# mainboard.net
KiCad netlist of a schematic drawn in EAGLE
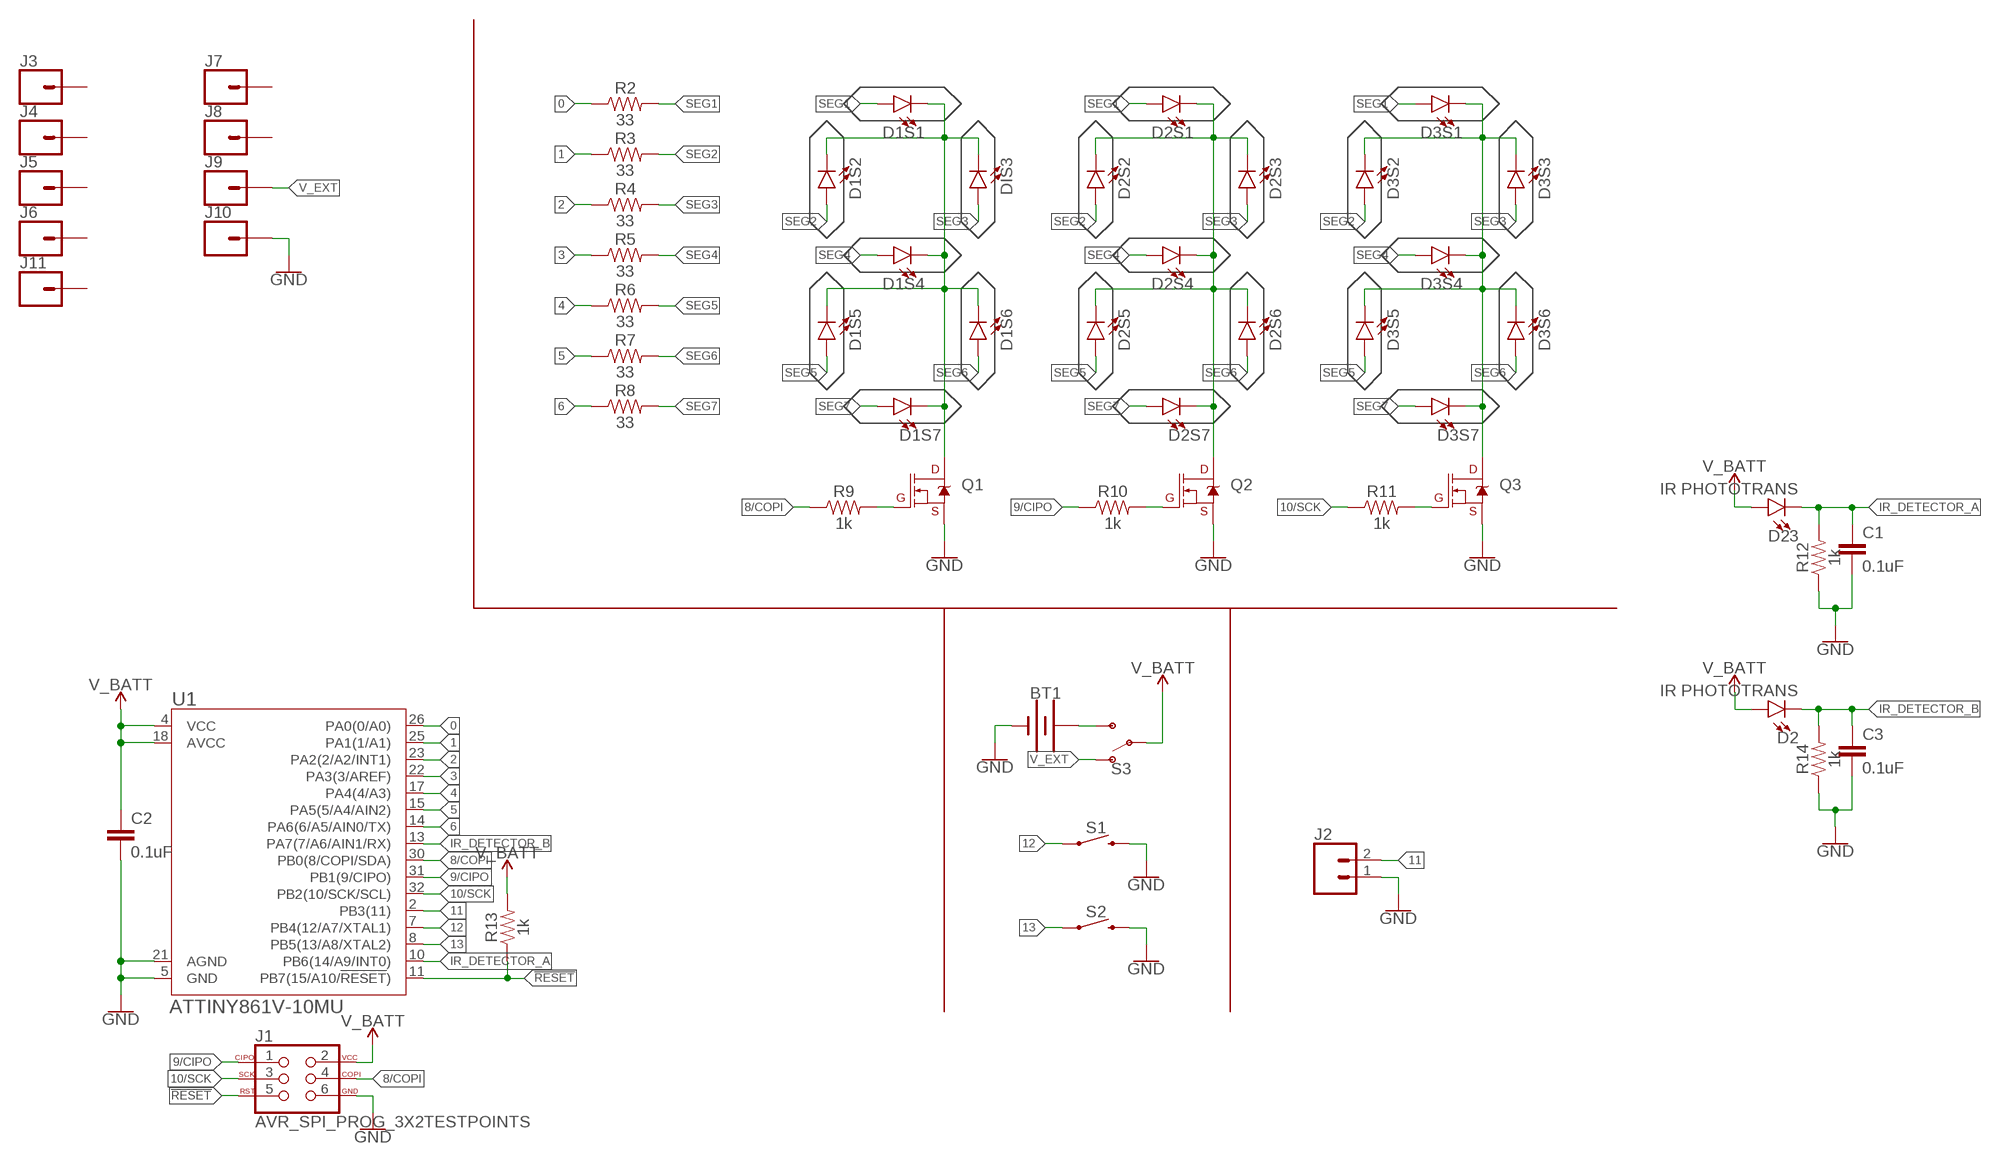
[diagram p0: schematic, sheet 1]

(export (version "E")
  (design (tool "Eeschema 10.0.6"))
  (components
    (comp (ref "BT1")
      (value "BATTERY-20MM_SMD_4LEGS_OVERPASTE_INNER")
      (footprint "eagle-import:BATTCON_20MM_4LEGS_OVERPASTE_INNER")
      (libsource (lib "eagle-import") (part "BATTERY-20MM_SMD_4LEGS_OVERPASTE_INNER"))
    )
    (comp (ref "C1")
      (value "0.1uF")
      (footprint "eagle-import:0603")
      (libsource (lib "eagle-import") (part "0.1UF-0603-25V-(+80/-20%)"))
    )
    (comp (ref "C2")
      (value "0.1uF")
      (footprint "eagle-import:0603")
      (libsource (lib "eagle-import") (part "0.1UF-0603-25V-(+80/-20%)"))
    )
    (comp (ref "C3")
      (value "0.1uF")
      (footprint "eagle-import:0603")
      (libsource (lib "eagle-import") (part "0.1UF-0603-25V-(+80/-20%)"))
    )
    (comp (ref "D1S1")
      (value "LED0603")
      (footprint "eagle-import:LED-0603")
      (libsource (lib "eagle-import") (part "LED0603"))
    )
    (comp (ref "D1S2")
      (value "LED0603")
      (footprint "eagle-import:LED-0603")
      (libsource (lib "eagle-import") (part "LED0603"))
    )
    (comp (ref "D1S4")
      (value "LED0603")
      (footprint "eagle-import:LED-0603")
      (libsource (lib "eagle-import") (part "LED0603"))
    )
    (comp (ref "D1S5")
      (value "LED0603")
      (footprint "eagle-import:LED-0603")
      (libsource (lib "eagle-import") (part "LED0603"))
    )
    (comp (ref "D1S6")
      (value "LED0603")
      (footprint "eagle-import:LED-0603")
      (libsource (lib "eagle-import") (part "LED0603"))
    )
    (comp (ref "D1S7")
      (value "LED0603")
      (footprint "eagle-import:LED-0603")
      (libsource (lib "eagle-import") (part "LED0603"))
    )
    (comp (ref "D2")
      (value "IR PHOTOTRANS")
      (footprint "eagle-import:LED-0603")
      (libsource (lib "eagle-import") (part "LED-IR0603"))
    )
    (comp (ref "D2S1")
      (value "LED0603")
      (footprint "eagle-import:LED-0603")
      (libsource (lib "eagle-import") (part "LED0603"))
    )
    (comp (ref "D2S2")
      (value "LED0603")
      (footprint "eagle-import:LED-0603")
      (libsource (lib "eagle-import") (part "LED0603"))
    )
    (comp (ref "D2S3")
      (value "LED0603")
      (footprint "eagle-import:LED-0603")
      (libsource (lib "eagle-import") (part "LED0603"))
    )
    (comp (ref "D2S4")
      (value "LED0603")
      (footprint "eagle-import:LED-0603")
      (libsource (lib "eagle-import") (part "LED0603"))
    )
    (comp (ref "D2S5")
      (value "LED0603")
      (footprint "eagle-import:LED-0603")
      (libsource (lib "eagle-import") (part "LED0603"))
    )
    (comp (ref "D2S6")
      (value "LED0603")
      (footprint "eagle-import:LED-0603")
      (libsource (lib "eagle-import") (part "LED0603"))
    )
    (comp (ref "D2S7")
      (value "LED0603")
      (footprint "eagle-import:LED-0603")
      (libsource (lib "eagle-import") (part "LED0603"))
    )
    (comp (ref "D3S1")
      (value "LED0603")
      (footprint "eagle-import:LED-0603")
      (libsource (lib "eagle-import") (part "LED0603"))
    )
    (comp (ref "D3S2")
      (value "LED0603")
      (footprint "eagle-import:LED-0603")
      (libsource (lib "eagle-import") (part "LED0603"))
    )
    (comp (ref "D3S3")
      (value "LED0603")
      (footprint "eagle-import:LED-0603")
      (libsource (lib "eagle-import") (part "LED0603"))
    )
    (comp (ref "D3S4")
      (value "LED0603")
      (footprint "eagle-import:LED-0603")
      (libsource (lib "eagle-import") (part "LED0603"))
    )
    (comp (ref "D3S5")
      (value "LED0603")
      (footprint "eagle-import:LED-0603")
      (libsource (lib "eagle-import") (part "LED0603"))
    )
    (comp (ref "D3S6")
      (value "LED0603")
      (footprint "eagle-import:LED-0603")
      (libsource (lib "eagle-import") (part "LED0603"))
    )
    (comp (ref "D3S7")
      (value "LED0603")
      (footprint "eagle-import:LED-0603")
      (libsource (lib "eagle-import") (part "LED0603"))
    )
    (comp (ref "D23")
      (value "IR PHOTOTRANS")
      (footprint "eagle-import:LED-0603")
      (libsource (lib "eagle-import") (part "LED-IR0603"))
    )
    (comp (ref "DIS3")
      (value "LED0603")
      (footprint "eagle-import:LED-0603")
      (libsource (lib "eagle-import") (part "LED0603"))
    )
    (comp (ref "J1")
      (value "AVR_SPI_PROG_3X2TESTPOINTS")
      (footprint "eagle-import:2X3_TEST_POINTS")
      (libsource (lib "eagle-import") (part "AVR_SPI_PROG_3X2TESTPOINTS"))
    )
    (comp (ref "J2")
      (value "CONN_02")
      (footprint "eagle-import:1X02")
      (libsource (lib "eagle-import") (part "CONN_02"))
    )
    (comp (ref "J3")
      (value "CONN_01")
      (footprint "eagle-import:1X01")
      (libsource (lib "eagle-import") (part "CONN_01"))
    )
    (comp (ref "J4")
      (value "CONN_01")
      (footprint "eagle-import:1X01")
      (libsource (lib "eagle-import") (part "CONN_01"))
    )
    (comp (ref "J5")
      (value "CONN_01")
      (footprint "eagle-import:1X01")
      (libsource (lib "eagle-import") (part "CONN_01"))
    )
    (comp (ref "J6")
      (value "CONN_01")
      (footprint "eagle-import:1X01")
      (libsource (lib "eagle-import") (part "CONN_01"))
    )
    (comp (ref "J7")
      (value "CONN_01")
      (footprint "eagle-import:1X01")
      (libsource (lib "eagle-import") (part "CONN_01"))
    )
    (comp (ref "J8")
      (value "CONN_01")
      (footprint "eagle-import:1X01")
      (libsource (lib "eagle-import") (part "CONN_01"))
    )
    (comp (ref "J9")
      (value "CONN_01")
      (footprint "eagle-import:1X01")
      (libsource (lib "eagle-import") (part "CONN_01"))
    )
    (comp (ref "J10")
      (value "CONN_01")
      (footprint "eagle-import:1X01")
      (libsource (lib "eagle-import") (part "CONN_01"))
    )
    (comp (ref "J11")
      (value "CONN_01")
      (footprint "eagle-import:1X01")
      (libsource (lib "eagle-import") (part "CONN_01"))
    )
    (comp (ref "Q1")
      (value "220mA/50V/3.5Ω")
      (footprint "eagle-import:SOT23-3")
      (libsource (lib "eagle-import") (part "MOSFET-NCH-BSS138"))
    )
    (comp (ref "Q2")
      (value "220mA/50V/3.5Ω")
      (footprint "eagle-import:SOT23-3")
      (libsource (lib "eagle-import") (part "MOSFET-NCH-BSS138"))
    )
    (comp (ref "Q3")
      (value "220mA/50V/3.5Ω")
      (footprint "eagle-import:SOT23-3")
      (libsource (lib "eagle-import") (part "MOSFET-NCH-BSS138"))
    )
    (comp (ref "R2")
      (value "33")
      (footprint "eagle-import:0603")
      (libsource (lib "eagle-import") (part "33OHM-0603-1/10W-1%"))
    )
    (comp (ref "R3")
      (value "33")
      (footprint "eagle-import:0603")
      (libsource (lib "eagle-import") (part "33OHM-0603-1/10W-1%"))
    )
    (comp (ref "R4")
      (value "33")
      (footprint "eagle-import:0603")
      (libsource (lib "eagle-import") (part "33OHM-0603-1/10W-1%"))
    )
    (comp (ref "R5")
      (value "33")
      (footprint "eagle-import:0603")
      (libsource (lib "eagle-import") (part "33OHM-0603-1/10W-1%"))
    )
    (comp (ref "R6")
      (value "33")
      (footprint "eagle-import:0603")
      (libsource (lib "eagle-import") (part "33OHM-0603-1/10W-1%"))
    )
    (comp (ref "R7")
      (value "33")
      (footprint "eagle-import:0603")
      (libsource (lib "eagle-import") (part "33OHM-0603-1/10W-1%"))
    )
    (comp (ref "R8")
      (value "33")
      (footprint "eagle-import:0603")
      (libsource (lib "eagle-import") (part "33OHM-0603-1/10W-1%"))
    )
    (comp (ref "R9")
      (value "1k")
      (footprint "eagle-import:0603")
      (libsource (lib "eagle-import") (part "1KOHM-0603-1/10W-1%"))
    )
    (comp (ref "R10")
      (value "1k")
      (footprint "eagle-import:0603")
      (libsource (lib "eagle-import") (part "1KOHM-0603-1/10W-1%"))
    )
    (comp (ref "R11")
      (value "1k")
      (footprint "eagle-import:0603")
      (libsource (lib "eagle-import") (part "1KOHM-0603-1/10W-1%"))
    )
    (comp (ref "R12")
      (value "1k")
      (footprint "eagle-import:0603")
      (libsource (lib "eagle-import") (part "1KOHM-0603-1/10W-1%"))
    )
    (comp (ref "R13")
      (value "1k")
      (footprint "eagle-import:0603")
      (libsource (lib "eagle-import") (part "1KOHM-0603-1/10W-1%"))
    )
    (comp (ref "R14")
      (value "1k")
      (footprint "eagle-import:0603")
      (libsource (lib "eagle-import") (part "1KOHM-0603-1/10W-1%"))
    )
    (comp (ref "S1")
      (value "MOMENTARY-SWITCH-SPST-SMD-5.2MM-TALL")
      (footprint "eagle-import:TACTILE_SWITCH_SMD_5.2MM")
      (libsource (lib "eagle-import") (part "MOMENTARY-SWITCH-SPST-SMD-5.2MM-TALL"))
    )
    (comp (ref "S2")
      (value "MOMENTARY-SWITCH-SPST-SMD-5.2MM-TALL")
      (footprint "eagle-import:TACTILE_SWITCH_SMD_5.2MM")
      (libsource (lib "eagle-import") (part "MOMENTARY-SWITCH-SPST-SMD-5.2MM-TALL"))
    )
    (comp (ref "S3")
      (value "SWITCH-SPDT-SMD-RIGHT-ANGLE")
      (footprint "eagle-import:SWITCH_SPST_SMD_A")
      (libsource (lib "eagle-import") (part "SWITCH-SPDT-SMD-RIGHT-ANGLE"))
    )
    (comp (ref "U1")
      (value "ATTINY861V-10MU")
      (footprint "eagle-import:32M1-A_ATM")
      (fields (field (name "COPYRIGHT") "Copyright (C) 2021 Ultra Librarian. All rights reserved."))
      (libsource (lib "eagle-import") (part "ATTINY861V-10MU"))
    )
  )
  (nets
    (net (code "1") (name "/~{RESET}") (class "Default")
      (node (ref "J1") (pin "5") (pinfunction "5_5") (pintype "passive"))
      (node (ref "R13") (pin "1") (pinfunction "1_1") (pintype "passive"))
      (node (ref "U1") (pin "11") (pinfunction "PB7(15/A10/~{RESET})_11") (pintype "bidirectional"))
    )
    (net (code "2") (name "0") (class "Default")
      (node (ref "R2") (pin "1") (pinfunction "1_1") (pintype "passive"))
      (node (ref "U1") (pin "26") (pinfunction "PA0(0/A0)_26") (pintype "bidirectional"))
    )
    (net (code "3") (name "1") (class "Default")
      (node (ref "R3") (pin "1") (pinfunction "1_1") (pintype "passive"))
      (node (ref "U1") (pin "25") (pinfunction "PA1(1/A1)_25") (pintype "bidirectional"))
    )
    (net (code "4") (name "2") (class "Default")
      (node (ref "R4") (pin "1") (pinfunction "1_1") (pintype "passive"))
      (node (ref "U1") (pin "23") (pinfunction "PA2(2/A2/INT1)_23") (pintype "bidirectional"))
    )
    (net (code "5") (name "3") (class "Default")
      (node (ref "R5") (pin "1") (pinfunction "1_1") (pintype "passive"))
      (node (ref "U1") (pin "22") (pinfunction "PA3(3/AREF)_22") (pintype "bidirectional"))
    )
    (net (code "6") (name "4") (class "Default")
      (node (ref "R6") (pin "1") (pinfunction "1_1") (pintype "passive"))
      (node (ref "U1") (pin "17") (pinfunction "PA4(4/A3)_17") (pintype "bidirectional"))
    )
    (net (code "7") (name "5") (class "Default")
      (node (ref "R7") (pin "1") (pinfunction "1_1") (pintype "passive"))
      (node (ref "U1") (pin "15") (pinfunction "PA5(5/A4/AIN2)_15") (pintype "bidirectional"))
    )
    (net (code "8") (name "6") (class "Default")
      (node (ref "R8") (pin "1") (pinfunction "1_1") (pintype "passive"))
      (node (ref "U1") (pin "14") (pinfunction "PA6(6/A5/AIN0/TX)_14") (pintype "bidirectional"))
    )
    (net (code "9") (name "8{slash}COPI") (class "Default")
      (node (ref "J1") (pin "4") (pinfunction "4_4") (pintype "passive"))
      (node (ref "R9") (pin "1") (pinfunction "1_1") (pintype "passive"))
      (node (ref "U1") (pin "30") (pinfunction "PB0(8/COPI/SDA)_30") (pintype "bidirectional"))
    )
    (net (code "10") (name "9{slash}CIPO") (class "Default")
      (node (ref "J1") (pin "1") (pinfunction "1_1") (pintype "passive"))
      (node (ref "R10") (pin "1") (pinfunction "1_1") (pintype "passive"))
      (node (ref "U1") (pin "31") (pinfunction "PB1(9/CIPO)_31") (pintype "bidirectional"))
    )
    (net (code "11") (name "10{slash}SCK") (class "Default")
      (node (ref "J1") (pin "3") (pinfunction "3_3") (pintype "passive"))
      (node (ref "R11") (pin "1") (pinfunction "1_1") (pintype "passive"))
      (node (ref "U1") (pin "32") (pinfunction "PB2(10/SCK/SCL)_32") (pintype "bidirectional"))
    )
    (net (code "12") (name "11") (class "Default")
      (node (ref "J2") (pin "2") (pinfunction "2_2") (pintype "passive"))
      (node (ref "U1") (pin "2") (pinfunction "PB3(11)_2") (pintype "bidirectional"))
    )
    (net (code "13") (name "12") (class "Default")
      (node (ref "S1") (pin "1") (pinfunction "1_1") (pintype "passive"))
      (node (ref "U1") (pin "7") (pinfunction "PB4(12/A7/XTAL1)_7") (pintype "bidirectional"))
    )
    (net (code "14") (name "13") (class "Default")
      (node (ref "S2") (pin "1") (pinfunction "1_1") (pintype "passive"))
      (node (ref "U1") (pin "8") (pinfunction "PB5(13/A8/XTAL2)_8") (pintype "bidirectional"))
    )
    (net (code "15") (name "GND") (class "Default")
      (node (ref "BT1") (pin "2") (pinfunction "-_2") (pintype "power_in"))
      (node (ref "C1") (pin "2") (pinfunction "2_2") (pintype "passive"))
      (node (ref "C2") (pin "2") (pinfunction "2_2") (pintype "passive"))
      (node (ref "C3") (pin "2") (pinfunction "2_2") (pintype "passive"))
      (node (ref "J1") (pin "6") (pinfunction "6_6") (pintype "passive"))
      (node (ref "J10") (pin "1") (pinfunction "1_1") (pintype "passive"))
      (node (ref "J2") (pin "1") (pinfunction "1_1") (pintype "passive"))
      (node (ref "Q1") (pin "2") (pinfunction "S_2") (pintype "bidirectional"))
      (node (ref "Q2") (pin "2") (pinfunction "S_2") (pintype "bidirectional"))
      (node (ref "Q3") (pin "2") (pinfunction "S_2") (pintype "bidirectional"))
      (node (ref "R12") (pin "1") (pinfunction "1_1") (pintype "passive"))
      (node (ref "R14") (pin "1") (pinfunction "1_1") (pintype "passive"))
      (node (ref "S1") (pin "3") (pinfunction "2_3") (pintype "passive"))
      (node (ref "S2") (pin "3") (pinfunction "2_3") (pintype "passive"))
      (node (ref "U1") (pin "21") (pinfunction "AGND_21") (pintype "power_in"))
      (node (ref "U1") (pin "5") (pinfunction "GND_5") (pintype "power_in"))
    )
    (net (code "16") (name "IR_DETECTOR_A") (class "Default")
      (node (ref "C1") (pin "1") (pinfunction "1_1") (pintype "passive"))
      (node (ref "D23") (pin "C") (pinfunction "C_C") (pintype "passive"))
      (node (ref "R12") (pin "2") (pinfunction "2_2") (pintype "passive"))
      (node (ref "U1") (pin "10") (pinfunction "PB6(14/A9/INT0)_10") (pintype "bidirectional"))
    )
    (net (code "17") (name "IR_DETECTOR_B") (class "Default")
      (node (ref "C3") (pin "1") (pinfunction "1_1") (pintype "passive"))
      (node (ref "D2") (pin "C") (pinfunction "C_C") (pintype "passive"))
      (node (ref "R14") (pin "2") (pinfunction "2_2") (pintype "passive"))
      (node (ref "U1") (pin "13") (pinfunction "PA7(7/A6/AIN1/RX)_13") (pintype "bidirectional"))
    )
    (net (code "18") (name "Net-(BT1-+)") (class "Default")
      (node (ref "BT1") (pin "1") (pinfunction "+_1") (pintype "power_in"))
      (node (ref "S3") (pin "3") (pinfunction "S_3") (pintype "passive"))
    )
    (net (code "19") (name "Net-(Q1-D)") (class "Default")
      (node (ref "D1S1") (pin "C") (pinfunction "C_C") (pintype "passive"))
      (node (ref "D1S2") (pin "C") (pinfunction "C_C") (pintype "passive"))
      (node (ref "D1S4") (pin "C") (pinfunction "C_C") (pintype "passive"))
      (node (ref "D1S5") (pin "C") (pinfunction "C_C") (pintype "passive"))
      (node (ref "D1S6") (pin "C") (pinfunction "C_C") (pintype "passive"))
      (node (ref "D1S7") (pin "C") (pinfunction "C_C") (pintype "passive"))
      (node (ref "DIS3") (pin "C") (pinfunction "C_C") (pintype "passive"))
      (node (ref "Q1") (pin "3") (pinfunction "D_3") (pintype "bidirectional"))
    )
    (net (code "20") (name "Net-(Q1-G)") (class "Default")
      (node (ref "Q1") (pin "1") (pinfunction "G_1") (pintype "bidirectional"))
      (node (ref "R9") (pin "2") (pinfunction "2_2") (pintype "passive"))
    )
    (net (code "21") (name "Net-(Q2-D)") (class "Default")
      (node (ref "D2S1") (pin "C") (pinfunction "C_C") (pintype "passive"))
      (node (ref "D2S2") (pin "C") (pinfunction "C_C") (pintype "passive"))
      (node (ref "D2S3") (pin "C") (pinfunction "C_C") (pintype "passive"))
      (node (ref "D2S4") (pin "C") (pinfunction "C_C") (pintype "passive"))
      (node (ref "D2S5") (pin "C") (pinfunction "C_C") (pintype "passive"))
      (node (ref "D2S6") (pin "C") (pinfunction "C_C") (pintype "passive"))
      (node (ref "D2S7") (pin "C") (pinfunction "C_C") (pintype "passive"))
      (node (ref "Q2") (pin "3") (pinfunction "D_3") (pintype "bidirectional"))
    )
    (net (code "22") (name "Net-(Q2-G)") (class "Default")
      (node (ref "Q2") (pin "1") (pinfunction "G_1") (pintype "bidirectional"))
      (node (ref "R10") (pin "2") (pinfunction "2_2") (pintype "passive"))
    )
    (net (code "23") (name "Net-(Q3-D)") (class "Default")
      (node (ref "D3S1") (pin "C") (pinfunction "C_C") (pintype "passive"))
      (node (ref "D3S2") (pin "C") (pinfunction "C_C") (pintype "passive"))
      (node (ref "D3S3") (pin "C") (pinfunction "C_C") (pintype "passive"))
      (node (ref "D3S4") (pin "C") (pinfunction "C_C") (pintype "passive"))
      (node (ref "D3S5") (pin "C") (pinfunction "C_C") (pintype "passive"))
      (node (ref "D3S6") (pin "C") (pinfunction "C_C") (pintype "passive"))
      (node (ref "D3S7") (pin "C") (pinfunction "C_C") (pintype "passive"))
      (node (ref "Q3") (pin "3") (pinfunction "D_3") (pintype "bidirectional"))
    )
    (net (code "24") (name "Net-(Q3-G)") (class "Default")
      (node (ref "Q3") (pin "1") (pinfunction "G_1") (pintype "bidirectional"))
      (node (ref "R11") (pin "2") (pinfunction "2_2") (pintype "passive"))
    )
    (net (code "25") (name "SEG1") (class "Default")
      (node (ref "D1S1") (pin "A") (pinfunction "A_A") (pintype "passive"))
      (node (ref "D2S1") (pin "A") (pinfunction "A_A") (pintype "passive"))
      (node (ref "D3S1") (pin "A") (pinfunction "A_A") (pintype "passive"))
      (node (ref "R2") (pin "2") (pinfunction "2_2") (pintype "passive"))
    )
    (net (code "26") (name "SEG2") (class "Default")
      (node (ref "D1S2") (pin "A") (pinfunction "A_A") (pintype "passive"))
      (node (ref "D2S2") (pin "A") (pinfunction "A_A") (pintype "passive"))
      (node (ref "D3S2") (pin "A") (pinfunction "A_A") (pintype "passive"))
      (node (ref "R3") (pin "2") (pinfunction "2_2") (pintype "passive"))
    )
    (net (code "27") (name "SEG3") (class "Default")
      (node (ref "D2S3") (pin "A") (pinfunction "A_A") (pintype "passive"))
      (node (ref "D3S3") (pin "A") (pinfunction "A_A") (pintype "passive"))
      (node (ref "DIS3") (pin "A") (pinfunction "A_A") (pintype "passive"))
      (node (ref "R4") (pin "2") (pinfunction "2_2") (pintype "passive"))
    )
    (net (code "28") (name "SEG4") (class "Default")
      (node (ref "D1S4") (pin "A") (pinfunction "A_A") (pintype "passive"))
      (node (ref "D2S4") (pin "A") (pinfunction "A_A") (pintype "passive"))
      (node (ref "D3S4") (pin "A") (pinfunction "A_A") (pintype "passive"))
      (node (ref "R5") (pin "2") (pinfunction "2_2") (pintype "passive"))
    )
    (net (code "29") (name "SEG5") (class "Default")
      (node (ref "D1S5") (pin "A") (pinfunction "A_A") (pintype "passive"))
      (node (ref "D2S5") (pin "A") (pinfunction "A_A") (pintype "passive"))
      (node (ref "D3S5") (pin "A") (pinfunction "A_A") (pintype "passive"))
      (node (ref "R6") (pin "2") (pinfunction "2_2") (pintype "passive"))
    )
    (net (code "30") (name "SEG6") (class "Default")
      (node (ref "D1S6") (pin "A") (pinfunction "A_A") (pintype "passive"))
      (node (ref "D2S6") (pin "A") (pinfunction "A_A") (pintype "passive"))
      (node (ref "D3S6") (pin "A") (pinfunction "A_A") (pintype "passive"))
      (node (ref "R7") (pin "2") (pinfunction "2_2") (pintype "passive"))
    )
    (net (code "31") (name "SEG7") (class "Default")
      (node (ref "D1S7") (pin "A") (pinfunction "A_A") (pintype "passive"))
      (node (ref "D2S7") (pin "A") (pinfunction "A_A") (pintype "passive"))
      (node (ref "D3S7") (pin "A") (pinfunction "A_A") (pintype "passive"))
      (node (ref "R8") (pin "2") (pinfunction "2_2") (pintype "passive"))
    )
    (net (code "32") (name "V_BATT") (class "Default")
      (node (ref "C2") (pin "1") (pinfunction "1_1") (pintype "passive"))
      (node (ref "D2") (pin "A") (pinfunction "A_A") (pintype "passive"))
      (node (ref "D23") (pin "A") (pinfunction "A_A") (pintype "passive"))
      (node (ref "J1") (pin "2") (pinfunction "2_2") (pintype "passive"))
      (node (ref "R13") (pin "2") (pinfunction "2_2") (pintype "passive"))
      (node (ref "S3") (pin "2") (pinfunction "P_2") (pintype "passive"))
      (node (ref "U1") (pin "18") (pinfunction "AVCC_18") (pintype "power_in"))
      (node (ref "U1") (pin "4") (pinfunction "VCC_4") (pintype "power_in"))
    )
    (net (code "33") (name "V_EXT") (class "Default")
      (node (ref "J9") (pin "1") (pinfunction "1_1") (pintype "passive"))
      (node (ref "S3") (pin "1") (pinfunction "O_1") (pintype "passive"))
    )
    (net (code "34") (name "unconnected-(J3-Pad1)") (class "Default")
      (node (ref "J3") (pin "1") (pinfunction "1_1") (pintype "passive"))
    )
    (net (code "35") (name "unconnected-(J4-Pad1)") (class "Default")
      (node (ref "J4") (pin "1") (pinfunction "1_1") (pintype "passive"))
    )
    (net (code "36") (name "unconnected-(J5-Pad1)") (class "Default")
      (node (ref "J5") (pin "1") (pinfunction "1_1") (pintype "passive"))
    )
    (net (code "37") (name "unconnected-(J6-Pad1)") (class "Default")
      (node (ref "J6") (pin "1") (pinfunction "1_1") (pintype "passive"))
    )
    (net (code "38") (name "unconnected-(J7-Pad1)") (class "Default")
      (node (ref "J7") (pin "1") (pinfunction "1_1") (pintype "passive"))
    )
    (net (code "39") (name "unconnected-(J8-Pad1)") (class "Default")
      (node (ref "J8") (pin "1") (pinfunction "1_1") (pintype "passive"))
    )
    (net (code "40") (name "unconnected-(J11-Pad1)") (class "Default")
      (node (ref "J11") (pin "1") (pinfunction "1_1") (pintype "passive"))
    )
  )
)
